# Clock_rev1.net
KiCad netlist of a schematic drawn in EAGLE
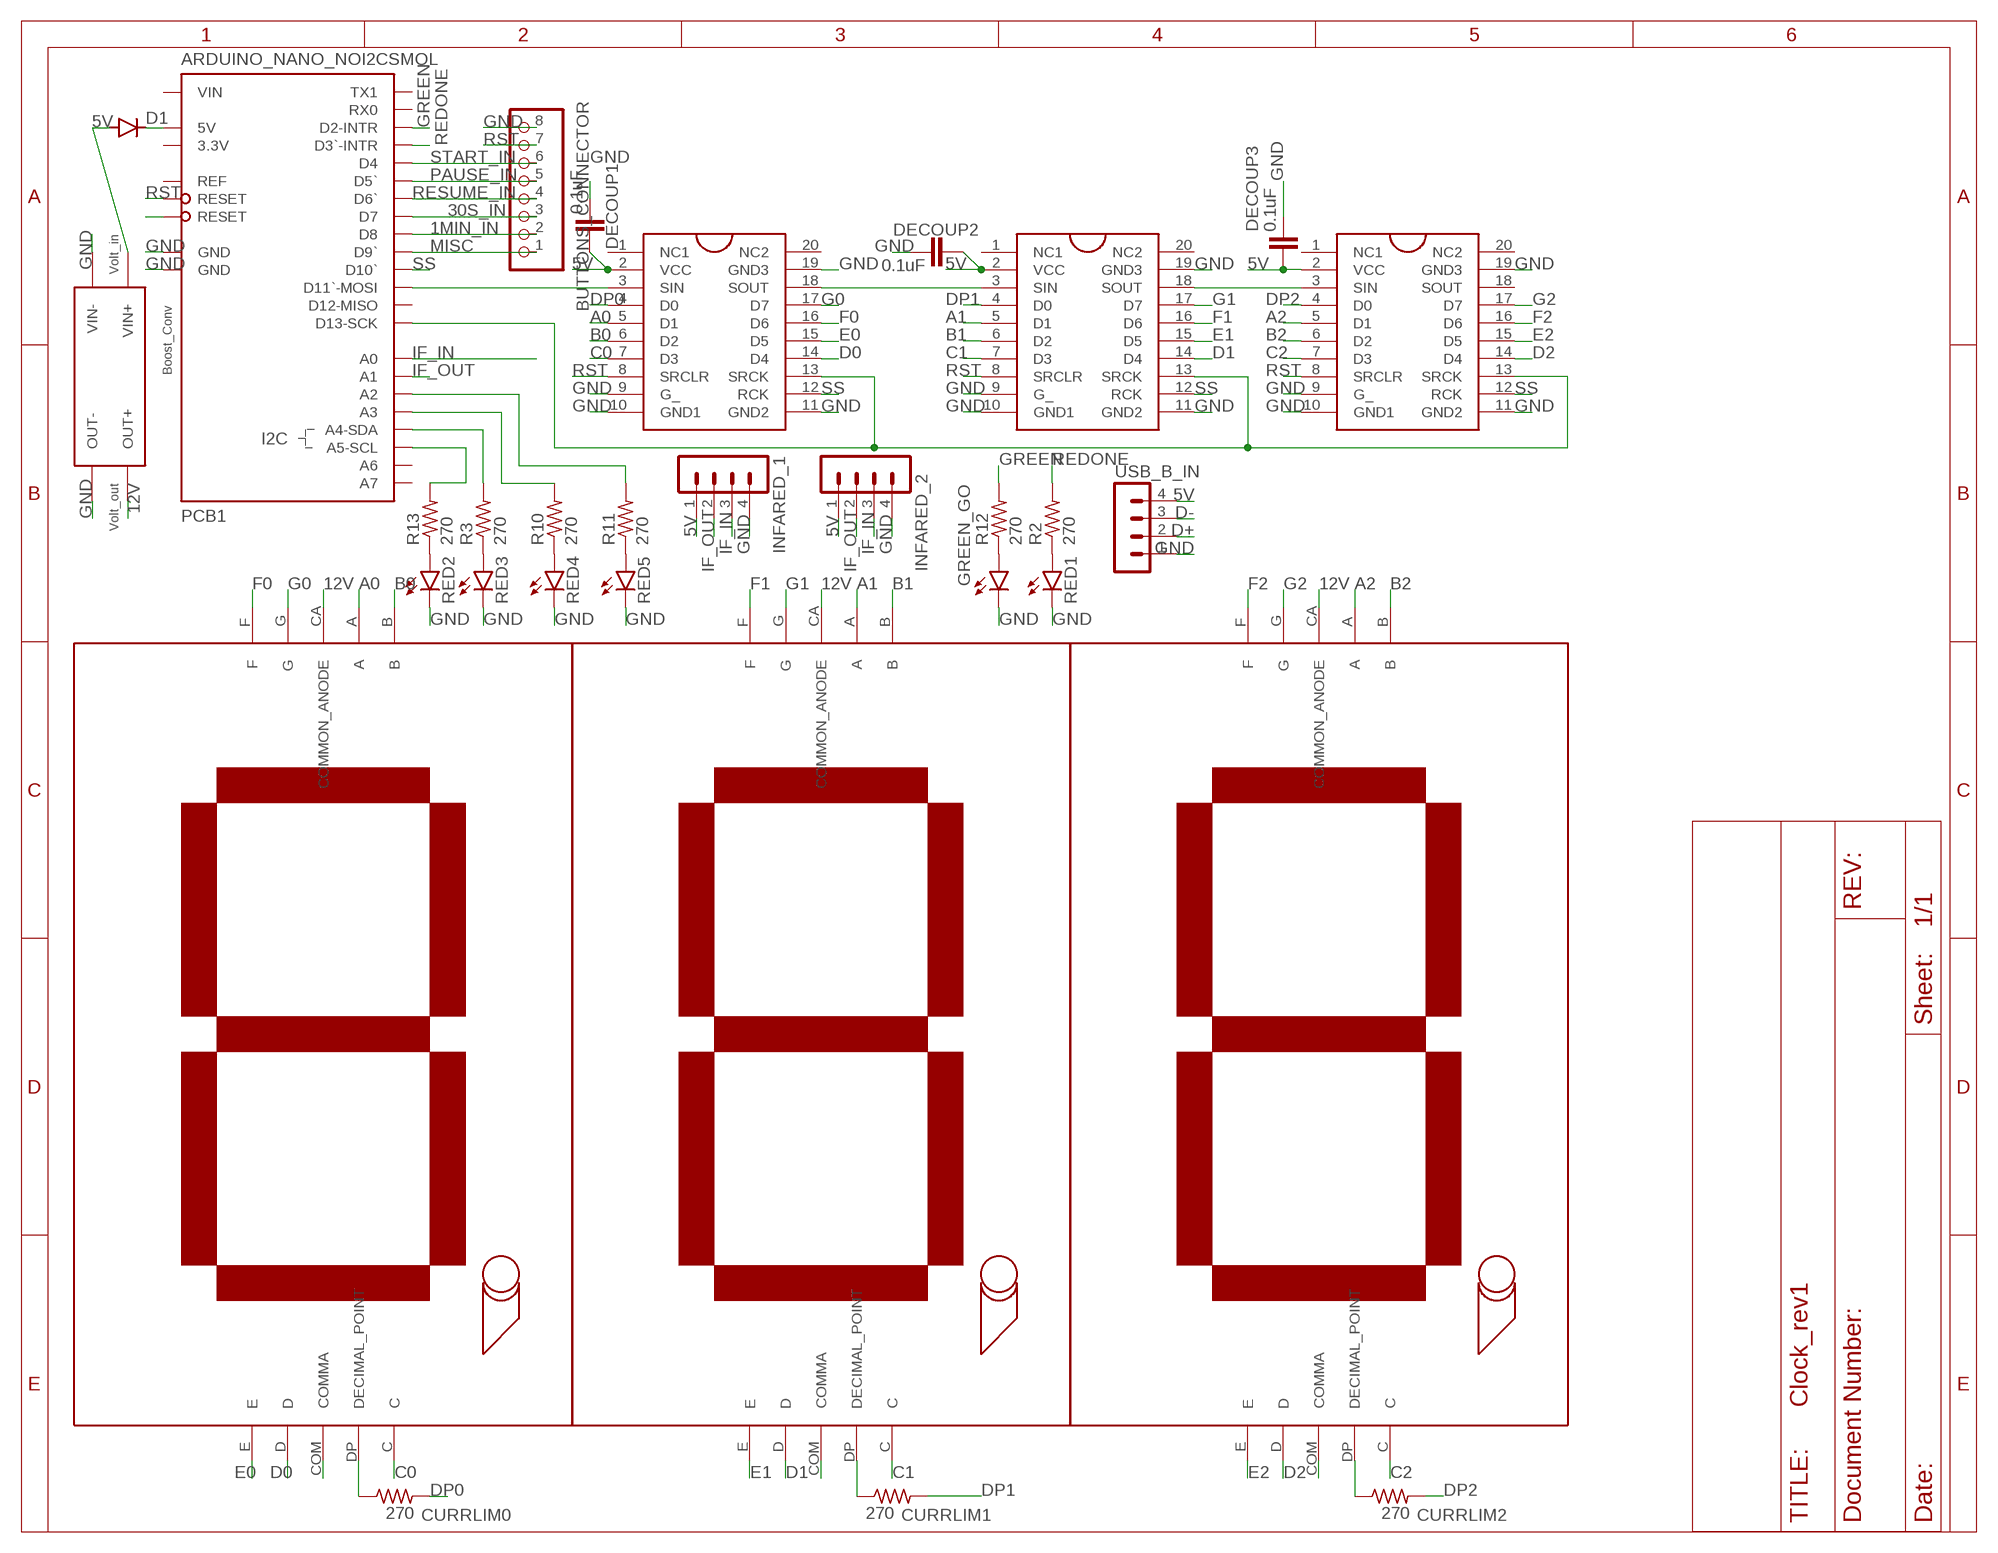
[diagram p0: schematic, sheet 1]

(export (version "E")
  (design (tool "Eeschema 10.0.6"))
  (components
    (comp (ref "BUTTONS_CONNECTOR")
      (value "PINHD-1X8/90")
      (footprint "eagle-import:1X08_90")
      (libsource (lib "eagle-import") (part "PINHD-1X8/90"))
    )
    (comp (ref "CURRLIM0")
      (value "270")
      (footprint "eagle-import:0207_10")
      (libsource (lib "eagle-import") (part "R-US_0207/10"))
    )
    (comp (ref "CURRLIM1")
      (value "270")
      (footprint "eagle-import:0207_10")
      (libsource (lib "eagle-import") (part "R-US_0207/10"))
    )
    (comp (ref "CURRLIM2")
      (value "270")
      (footprint "eagle-import:0207_10")
      (libsource (lib "eagle-import") (part "R-US_0207/10"))
    )
    (comp (ref "D1")
      (value "1N4148DO35-7")
      (footprint "eagle-import:DO35-7")
      (libsource (lib "eagle-import") (part "1N4148DO35-7"))
    )
    (comp (ref "DECOUP1")
      (value "0.1uF")
      (footprint "eagle-import:C2.5-2")
      (libsource (lib "eagle-import") (part "C2.5/2"))
    )
    (comp (ref "DECOUP2")
      (value "0.1uF")
      (footprint "eagle-import:C2.5-2")
      (libsource (lib "eagle-import") (part "C2.5/2"))
    )
    (comp (ref "DECOUP3")
      (value "0.1uF")
      (footprint "eagle-import:C2.5-2")
      (libsource (lib "eagle-import") (part "C2.5/2"))
    )
    (comp (ref "GREEN_GO")
      (value "LED5MM")
      (footprint "eagle-import:LED5MM")
      (libsource (lib "eagle-import") (part "LED5MM"))
    )
    (comp (ref "INFARED_1")
      (value "MA04-1")
      (footprint "eagle-import:MA04-1")
      (libsource (lib "eagle-import") (part "MA04-1"))
    )
    (comp (ref "INFARED_2")
      (value "MA04-1")
      (footprint "eagle-import:MA04-1")
      (libsource (lib "eagle-import") (part "MA04-1"))
    )
    (comp (ref "MINUTES")
      (value "7SEG_LED_A-3001SR")
      (footprint "eagle-import:7SEG_LED")
      (libsource (lib "eagle-import") (part "7SEG_LED_A-3001SR"))
    )
    (comp (ref "PCB1")
      (value "ARDUINO_NANO_NOI2CSMOL")
      (footprint "eagle-import:ARDUINO_NANO_SMOL")
      (libsource (lib "eagle-import") (part "ARDUINO_NANO_NOI2CSMOL"))
    )
    (comp (ref "R2")
      (value "270")
      (footprint "eagle-import:0207_10")
      (libsource (lib "eagle-import") (part "R-US_0207/10"))
    )
    (comp (ref "R3")
      (value "270")
      (footprint "eagle-import:0207_10")
      (libsource (lib "eagle-import") (part "R-US_0207/10"))
    )
    (comp (ref "R10")
      (value "270")
      (footprint "eagle-import:0207_10")
      (libsource (lib "eagle-import") (part "R-US_0207/10"))
    )
    (comp (ref "R11")
      (value "270")
      (footprint "eagle-import:0207_10")
      (libsource (lib "eagle-import") (part "R-US_0207/10"))
    )
    (comp (ref "R12")
      (value "270")
      (footprint "eagle-import:0207_10")
      (libsource (lib "eagle-import") (part "R-US_0207/10"))
    )
    (comp (ref "R13")
      (value "270")
      (footprint "eagle-import:0207_10")
      (libsource (lib "eagle-import") (part "R-US_0207/10"))
    )
    (comp (ref "RED1")
      (value "LED5MM")
      (footprint "eagle-import:LED5MM")
      (libsource (lib "eagle-import") (part "LED5MM"))
    )
    (comp (ref "RED2")
      (value "LED5MM")
      (footprint "eagle-import:LED5MM")
      (libsource (lib "eagle-import") (part "LED5MM"))
    )
    (comp (ref "RED3")
      (value "LED5MM")
      (footprint "eagle-import:LED5MM")
      (libsource (lib "eagle-import") (part "LED5MM"))
    )
    (comp (ref "RED4")
      (value "LED5MM")
      (footprint "eagle-import:LED5MM")
      (libsource (lib "eagle-import") (part "LED5MM"))
    )
    (comp (ref "RED5")
      (value "LED5MM")
      (footprint "eagle-import:LED5MM")
      (libsource (lib "eagle-import") (part "LED5MM"))
    )
    (comp (ref "SECONDS_ONES")
      (value "7SEG_LED_A-3001SR")
      (footprint "eagle-import:7SEG_LED")
      (libsource (lib "eagle-import") (part "7SEG_LED_A-3001SR"))
    )
    (comp (ref "SECONDS_TENS")
      (value "7SEG_LED_A-3001SR")
      (footprint "eagle-import:7SEG_LED")
      (libsource (lib "eagle-import") (part "7SEG_LED_A-3001SR"))
    )
    (comp (ref "SP0")
      (value "SHIFT_REGISTER_TPIC6C595")
      (footprint "eagle-import:SHIFT_REGISTER")
      (libsource (lib "eagle-import") (part "SHIFT_REGISTER_TPIC6C595"))
    )
    (comp (ref "SP1")
      (value "SHIFT_REGISTER_TPIC6C595")
      (footprint "eagle-import:SHIFT_REGISTER")
      (libsource (lib "eagle-import") (part "SHIFT_REGISTER_TPIC6C595"))
    )
    (comp (ref "SP2")
      (value "SHIFT_REGISTER_TPIC6C595")
      (footprint "eagle-import:SHIFT_REGISTER")
      (libsource (lib "eagle-import") (part "SHIFT_REGISTER_TPIC6C595"))
    )
    (comp (ref "U$4")
      (value "BOOST_CONV")
      (footprint "eagle-import:BOOST_CONV")
      (libsource (lib "eagle-import") (part "BOOST_CONV"))
    )
    (comp (ref "USB_B_IN")
      (value "MA04-1")
      (footprint "eagle-import:MA04-1")
      (libsource (lib "eagle-import") (part "MA04-1"))
    )
  )
  (nets
    (net (code "1") (name "/1MIN_IN") (class "Default")
      (node (ref "BUTTONS_CONNECTOR") (pin "2") (pinfunction "2_2") (pintype "passive"))
      (node (ref "PCB1") (pin "D8") (pinfunction "D8_D8") (pintype "bidirectional"))
    )
    (net (code "2") (name "/5V") (class "Default")
      (node (ref "D1") (pin "A") (pinfunction "A_A") (pintype "passive"))
      (node (ref "DECOUP1") (pin "2") (pinfunction "2_2") (pintype "passive"))
      (node (ref "DECOUP2") (pin "2") (pinfunction "2_2") (pintype "passive"))
      (node (ref "DECOUP3") (pin "2") (pinfunction "2_2") (pintype "passive"))
      (node (ref "INFARED_1") (pin "1") (pinfunction "1_1") (pintype "passive"))
      (node (ref "INFARED_2") (pin "1") (pinfunction "1_1") (pintype "passive"))
      (node (ref "SP0") (pin "2") (pinfunction "VCC_2") (pintype "bidirectional"))
      (node (ref "SP1") (pin "2") (pinfunction "VCC_2") (pintype "bidirectional"))
      (node (ref "SP2") (pin "2") (pinfunction "VCC_2") (pintype "bidirectional"))
      (node (ref "U$4") (pin "P$2") (pinfunction "VIN+_P$2") (pintype "bidirectional"))
      (node (ref "USB_B_IN") (pin "4") (pinfunction "4_4") (pintype "passive"))
    )
    (net (code "3") (name "/12V") (class "Default")
      (node (ref "MINUTES") (pin "CA") (pinfunction "COMMON_ANODE_CA") (pintype "bidirectional"))
      (node (ref "SECONDS_ONES") (pin "CA") (pinfunction "COMMON_ANODE_CA") (pintype "bidirectional"))
      (node (ref "SECONDS_TENS") (pin "CA") (pinfunction "COMMON_ANODE_CA") (pintype "bidirectional"))
      (node (ref "U$4") (pin "P$3") (pinfunction "OUT+_P$3") (pintype "bidirectional"))
    )
    (net (code "4") (name "/30S_IN") (class "Default")
      (node (ref "BUTTONS_CONNECTOR") (pin "3") (pinfunction "3_3") (pintype "passive"))
      (node (ref "PCB1") (pin "D7") (pinfunction "D7_D7") (pintype "bidirectional"))
    )
    (net (code "5") (name "/A0") (class "Default")
      (node (ref "MINUTES") (pin "A") (pinfunction "A_A") (pintype "bidirectional"))
      (node (ref "SP0") (pin "5") (pinfunction "D1_5") (pintype "bidirectional"))
    )
    (net (code "6") (name "/A1") (class "Default")
      (node (ref "SECONDS_TENS") (pin "A") (pinfunction "A_A") (pintype "bidirectional"))
      (node (ref "SP1") (pin "5") (pinfunction "D1_5") (pintype "bidirectional"))
    )
    (net (code "7") (name "/A2") (class "Default")
      (node (ref "SECONDS_ONES") (pin "A") (pinfunction "A_A") (pintype "bidirectional"))
      (node (ref "SP2") (pin "5") (pinfunction "D1_5") (pintype "bidirectional"))
    )
    (net (code "8") (name "/B0") (class "Default")
      (node (ref "MINUTES") (pin "B") (pinfunction "B_B") (pintype "bidirectional"))
      (node (ref "SP0") (pin "6") (pinfunction "D2_6") (pintype "bidirectional"))
    )
    (net (code "9") (name "/B1") (class "Default")
      (node (ref "SECONDS_TENS") (pin "B") (pinfunction "B_B") (pintype "bidirectional"))
      (node (ref "SP1") (pin "6") (pinfunction "D2_6") (pintype "bidirectional"))
    )
    (net (code "10") (name "/B2") (class "Default")
      (node (ref "SECONDS_ONES") (pin "B") (pinfunction "B_B") (pintype "bidirectional"))
      (node (ref "SP2") (pin "6") (pinfunction "D2_6") (pintype "bidirectional"))
    )
    (net (code "11") (name "/C0") (class "Default")
      (node (ref "MINUTES") (pin "C") (pinfunction "C_C") (pintype "bidirectional"))
      (node (ref "SP0") (pin "7") (pinfunction "D3_7") (pintype "bidirectional"))
    )
    (net (code "12") (name "/C1") (class "Default")
      (node (ref "SECONDS_TENS") (pin "C") (pinfunction "C_C") (pintype "bidirectional"))
      (node (ref "SP1") (pin "7") (pinfunction "D3_7") (pintype "bidirectional"))
    )
    (net (code "13") (name "/C2") (class "Default")
      (node (ref "SECONDS_ONES") (pin "C") (pinfunction "C_C") (pintype "bidirectional"))
      (node (ref "SP2") (pin "7") (pinfunction "D3_7") (pintype "bidirectional"))
    )
    (net (code "14") (name "/D+") (class "Default")
      (node (ref "USB_B_IN") (pin "2") (pinfunction "2_2") (pintype "passive"))
    )
    (net (code "15") (name "/D-") (class "Default")
      (node (ref "USB_B_IN") (pin "3") (pinfunction "3_3") (pintype "passive"))
    )
    (net (code "16") (name "/D0") (class "Default")
      (node (ref "MINUTES") (pin "D") (pinfunction "D_D") (pintype "bidirectional"))
      (node (ref "SP0") (pin "14") (pinfunction "D4_14") (pintype "bidirectional"))
    )
    (net (code "17") (name "/D1") (class "Default")
      (node (ref "SECONDS_TENS") (pin "D") (pinfunction "D_D") (pintype "bidirectional"))
      (node (ref "SP1") (pin "14") (pinfunction "D4_14") (pintype "bidirectional"))
    )
    (net (code "18") (name "/D2") (class "Default")
      (node (ref "SECONDS_ONES") (pin "D") (pinfunction "D_D") (pintype "bidirectional"))
      (node (ref "SP2") (pin "14") (pinfunction "D4_14") (pintype "bidirectional"))
    )
    (net (code "19") (name "/DP0") (class "Default")
      (node (ref "CURRLIM0") (pin "2") (pinfunction "2_2") (pintype "passive"))
      (node (ref "SP0") (pin "4") (pinfunction "D0_4") (pintype "bidirectional"))
    )
    (net (code "20") (name "/DP1") (class "Default")
      (node (ref "CURRLIM1") (pin "2") (pinfunction "2_2") (pintype "passive"))
      (node (ref "SP1") (pin "4") (pinfunction "D0_4") (pintype "bidirectional"))
    )
    (net (code "21") (name "/DP2") (class "Default")
      (node (ref "CURRLIM2") (pin "2") (pinfunction "2_2") (pintype "passive"))
      (node (ref "SP2") (pin "4") (pinfunction "D0_4") (pintype "bidirectional"))
    )
    (net (code "22") (name "/E0") (class "Default")
      (node (ref "MINUTES") (pin "E") (pinfunction "E_E") (pintype "bidirectional"))
      (node (ref "SP0") (pin "15") (pinfunction "D5_15") (pintype "bidirectional"))
    )
    (net (code "23") (name "/E1") (class "Default")
      (node (ref "SECONDS_TENS") (pin "E") (pinfunction "E_E") (pintype "bidirectional"))
      (node (ref "SP1") (pin "15") (pinfunction "D5_15") (pintype "bidirectional"))
    )
    (net (code "24") (name "/E2") (class "Default")
      (node (ref "SECONDS_ONES") (pin "E") (pinfunction "E_E") (pintype "bidirectional"))
      (node (ref "SP2") (pin "15") (pinfunction "D5_15") (pintype "bidirectional"))
    )
    (net (code "25") (name "/F0") (class "Default")
      (node (ref "MINUTES") (pin "F") (pinfunction "F_F") (pintype "bidirectional"))
      (node (ref "SP0") (pin "16") (pinfunction "D6_16") (pintype "bidirectional"))
    )
    (net (code "26") (name "/F1") (class "Default")
      (node (ref "SECONDS_TENS") (pin "F") (pinfunction "F_F") (pintype "bidirectional"))
      (node (ref "SP1") (pin "16") (pinfunction "D6_16") (pintype "bidirectional"))
    )
    (net (code "27") (name "/F2") (class "Default")
      (node (ref "SECONDS_ONES") (pin "F") (pinfunction "F_F") (pintype "bidirectional"))
      (node (ref "SP2") (pin "16") (pinfunction "D6_16") (pintype "bidirectional"))
    )
    (net (code "28") (name "/G0") (class "Default")
      (node (ref "MINUTES") (pin "G") (pinfunction "G_G") (pintype "bidirectional"))
      (node (ref "SP0") (pin "17") (pinfunction "D7_17") (pintype "bidirectional"))
    )
    (net (code "29") (name "/G1") (class "Default")
      (node (ref "SECONDS_TENS") (pin "G") (pinfunction "G_G") (pintype "bidirectional"))
      (node (ref "SP1") (pin "17") (pinfunction "D7_17") (pintype "bidirectional"))
    )
    (net (code "30") (name "/G2") (class "Default")
      (node (ref "SECONDS_ONES") (pin "G") (pinfunction "G_G") (pintype "bidirectional"))
      (node (ref "SP2") (pin "17") (pinfunction "D7_17") (pintype "bidirectional"))
    )
    (net (code "31") (name "/GND") (class "Default")
      (node (ref "BUTTONS_CONNECTOR") (pin "8") (pinfunction "8_8") (pintype "passive"))
      (node (ref "DECOUP1") (pin "1") (pinfunction "1_1") (pintype "passive"))
      (node (ref "DECOUP2") (pin "1") (pinfunction "1_1") (pintype "passive"))
      (node (ref "DECOUP3") (pin "1") (pinfunction "1_1") (pintype "passive"))
      (node (ref "GREEN_GO") (pin "K") (pinfunction "C_K") (pintype "passive"))
      (node (ref "INFARED_1") (pin "4") (pinfunction "4_4") (pintype "passive"))
      (node (ref "INFARED_2") (pin "4") (pinfunction "4_4") (pintype "passive"))
      (node (ref "PCB1") (pin "GND") (pinfunction "GND_GND") (pintype "bidirectional"))
      (node (ref "PCB1") (pin "GND@2") (pinfunction "GND_GND@2") (pintype "bidirectional"))
      (node (ref "RED1") (pin "K") (pinfunction "C_K") (pintype "passive"))
      (node (ref "RED2") (pin "K") (pinfunction "C_K") (pintype "passive"))
      (node (ref "RED3") (pin "K") (pinfunction "C_K") (pintype "passive"))
      (node (ref "RED4") (pin "K") (pinfunction "C_K") (pintype "passive"))
      (node (ref "RED5") (pin "K") (pinfunction "C_K") (pintype "passive"))
      (node (ref "SP0") (pin "10") (pinfunction "GND1_10") (pintype "bidirectional"))
      (node (ref "SP0") (pin "11") (pinfunction "GND2_11") (pintype "bidirectional"))
      (node (ref "SP0") (pin "19") (pinfunction "GND3_19") (pintype "bidirectional"))
      (node (ref "SP0") (pin "9") (pinfunction "G__9") (pintype "bidirectional"))
      (node (ref "SP1") (pin "10") (pinfunction "GND1_10") (pintype "bidirectional"))
      (node (ref "SP1") (pin "11") (pinfunction "GND2_11") (pintype "bidirectional"))
      (node (ref "SP1") (pin "19") (pinfunction "GND3_19") (pintype "bidirectional"))
      (node (ref "SP1") (pin "9") (pinfunction "G__9") (pintype "bidirectional"))
      (node (ref "SP2") (pin "10") (pinfunction "GND1_10") (pintype "bidirectional"))
      (node (ref "SP2") (pin "11") (pinfunction "GND2_11") (pintype "bidirectional"))
      (node (ref "SP2") (pin "19") (pinfunction "GND3_19") (pintype "bidirectional"))
      (node (ref "SP2") (pin "9") (pinfunction "G__9") (pintype "bidirectional"))
      (node (ref "U$4") (pin "P$1") (pinfunction "VIN-_P$1") (pintype "bidirectional"))
      (node (ref "U$4") (pin "P$4") (pinfunction "OUT-_P$4") (pintype "bidirectional"))
      (node (ref "USB_B_IN") (pin "1") (pinfunction "1_1") (pintype "passive"))
    )
    (net (code "32") (name "/GREEN") (class "Default")
      (node (ref "PCB1") (pin "D2") (pinfunction "D2-INTR_D2") (pintype "bidirectional"))
      (node (ref "R12") (pin "2") (pinfunction "2_2") (pintype "passive"))
    )
    (net (code "33") (name "/IF_IN") (class "Default")
      (node (ref "INFARED_1") (pin "3") (pinfunction "3_3") (pintype "passive"))
      (node (ref "INFARED_2") (pin "3") (pinfunction "3_3") (pintype "passive"))
      (node (ref "PCB1") (pin "A0") (pinfunction "A0_A0") (pintype "bidirectional"))
    )
    (net (code "34") (name "/IF_OUT") (class "Default")
      (node (ref "INFARED_1") (pin "2") (pinfunction "2_2") (pintype "passive"))
      (node (ref "INFARED_2") (pin "2") (pinfunction "2_2") (pintype "passive"))
      (node (ref "PCB1") (pin "A1") (pinfunction "A1_A1") (pintype "bidirectional"))
    )
    (net (code "35") (name "/MISC") (class "Default")
      (node (ref "BUTTONS_CONNECTOR") (pin "1") (pinfunction "1_1") (pintype "passive"))
      (node (ref "PCB1") (pin "D9") (pinfunction "D9`_D9") (pintype "bidirectional"))
    )
    (net (code "36") (name "/PAUSE_IN") (class "Default")
      (node (ref "BUTTONS_CONNECTOR") (pin "5") (pinfunction "5_5") (pintype "passive"))
      (node (ref "PCB1") (pin "D5") (pinfunction "D5`_D5") (pintype "bidirectional"))
    )
    (net (code "37") (name "/REDONE") (class "Default")
      (node (ref "PCB1") (pin "D3") (pinfunction "D3`-INTR_D3") (pintype "bidirectional"))
      (node (ref "R2") (pin "2") (pinfunction "2_2") (pintype "passive"))
    )
    (net (code "38") (name "/RESUME_IN") (class "Default")
      (node (ref "BUTTONS_CONNECTOR") (pin "4") (pinfunction "4_4") (pintype "passive"))
      (node (ref "PCB1") (pin "D6") (pinfunction "D6`_D6") (pintype "bidirectional"))
    )
    (net (code "39") (name "/RST") (class "Default")
      (node (ref "BUTTONS_CONNECTOR") (pin "7") (pinfunction "7_7") (pintype "passive"))
      (node (ref "PCB1") (pin "RESET") (pinfunction "RESET_RESET") (pintype "bidirectional"))
      (node (ref "SP0") (pin "8") (pinfunction "SRCLR_8") (pintype "bidirectional"))
      (node (ref "SP1") (pin "8") (pinfunction "SRCLR_8") (pintype "bidirectional"))
      (node (ref "SP2") (pin "8") (pinfunction "SRCLR_8") (pintype "bidirectional"))
    )
    (net (code "40") (name "/SS") (class "Default")
      (node (ref "PCB1") (pin "D10") (pinfunction "D10`_D10") (pintype "bidirectional"))
      (node (ref "SP0") (pin "12") (pinfunction "RCK_12") (pintype "bidirectional"))
      (node (ref "SP1") (pin "12") (pinfunction "RCK_12") (pintype "bidirectional"))
      (node (ref "SP2") (pin "12") (pinfunction "RCK_12") (pintype "bidirectional"))
    )
    (net (code "41") (name "/START_IN") (class "Default")
      (node (ref "BUTTONS_CONNECTOR") (pin "6") (pinfunction "6_6") (pintype "passive"))
      (node (ref "PCB1") (pin "D4") (pinfunction "D4_D4") (pintype "bidirectional"))
    )
    (net (code "42") (name "Net-(D1-PadC)") (class "Default")
      (node (ref "D1") (pin "C") (pinfunction "C_C") (pintype "passive"))
      (node (ref "PCB1") (pin "5V") (pinfunction "5V_5V") (pintype "bidirectional"))
    )
    (net (code "43") (name "Net-(GREEN_GO-PadA)") (class "Default")
      (node (ref "GREEN_GO") (pin "A") (pinfunction "A_A") (pintype "passive"))
      (node (ref "R12") (pin "1") (pinfunction "1_1") (pintype "passive"))
    )
    (net (code "44") (name "Net-(MINUTES-DECIMAL_POINT)") (class "Default")
      (node (ref "CURRLIM0") (pin "1") (pinfunction "1_1") (pintype "passive"))
      (node (ref "MINUTES") (pin "DP") (pinfunction "DECIMAL_POINT_DP") (pintype "bidirectional"))
    )
    (net (code "45") (name "Net-(PCB1-A4-SDA)") (class "Default")
      (node (ref "PCB1") (pin "A4") (pinfunction "A4-SDA_A4") (pintype "bidirectional"))
      (node (ref "R3") (pin "2") (pinfunction "2_2") (pintype "passive"))
    )
    (net (code "46") (name "Net-(PCB1-A5-SCL)") (class "Default")
      (node (ref "PCB1") (pin "A5") (pinfunction "A5-SCL_A5") (pintype "bidirectional"))
      (node (ref "R13") (pin "2") (pinfunction "2_2") (pintype "passive"))
    )
    (net (code "47") (name "Net-(PCB1-D11`-MOSI)") (class "Default")
      (node (ref "PCB1") (pin "D11") (pinfunction "D11`-MOSI_D11") (pintype "bidirectional"))
      (node (ref "SP0") (pin "3") (pinfunction "SIN_3") (pintype "bidirectional"))
    )
    (net (code "48") (name "Net-(PCB1-D13-SCK)") (class "Default")
      (node (ref "PCB1") (pin "D13") (pinfunction "D13-SCK_D13") (pintype "bidirectional"))
      (node (ref "SP0") (pin "13") (pinfunction "SRCK_13") (pintype "bidirectional"))
      (node (ref "SP1") (pin "13") (pinfunction "SRCK_13") (pintype "bidirectional"))
      (node (ref "SP2") (pin "13") (pinfunction "SRCK_13") (pintype "bidirectional"))
    )
    (net (code "49") (name "Net-(PCB1-PadA2)") (class "Default")
      (node (ref "PCB1") (pin "A2") (pinfunction "A2_A2") (pintype "bidirectional"))
      (node (ref "R11") (pin "2") (pinfunction "2_2") (pintype "passive"))
    )
    (net (code "50") (name "Net-(PCB1-PadA3)") (class "Default")
      (node (ref "PCB1") (pin "A3") (pinfunction "A3_A3") (pintype "bidirectional"))
      (node (ref "R10") (pin "2") (pinfunction "2_2") (pintype "passive"))
    )
    (net (code "51") (name "Net-(R2-Pad1)") (class "Default")
      (node (ref "R2") (pin "1") (pinfunction "1_1") (pintype "passive"))
      (node (ref "RED1") (pin "A") (pinfunction "A_A") (pintype "passive"))
    )
    (net (code "52") (name "Net-(R3-Pad1)") (class "Default")
      (node (ref "R3") (pin "1") (pinfunction "1_1") (pintype "passive"))
      (node (ref "RED3") (pin "A") (pinfunction "A_A") (pintype "passive"))
    )
    (net (code "53") (name "Net-(R10-Pad1)") (class "Default")
      (node (ref "R10") (pin "1") (pinfunction "1_1") (pintype "passive"))
      (node (ref "RED4") (pin "A") (pinfunction "A_A") (pintype "passive"))
    )
    (net (code "54") (name "Net-(R11-Pad1)") (class "Default")
      (node (ref "R11") (pin "1") (pinfunction "1_1") (pintype "passive"))
      (node (ref "RED5") (pin "A") (pinfunction "A_A") (pintype "passive"))
    )
    (net (code "55") (name "Net-(R13-Pad1)") (class "Default")
      (node (ref "R13") (pin "1") (pinfunction "1_1") (pintype "passive"))
      (node (ref "RED2") (pin "A") (pinfunction "A_A") (pintype "passive"))
    )
    (net (code "56") (name "Net-(SECONDS_ONES-DECIMAL_POINT)") (class "Default")
      (node (ref "CURRLIM2") (pin "1") (pinfunction "1_1") (pintype "passive"))
      (node (ref "SECONDS_ONES") (pin "DP") (pinfunction "DECIMAL_POINT_DP") (pintype "bidirectional"))
    )
    (net (code "57") (name "Net-(SECONDS_TENS-DECIMAL_POINT)") (class "Default")
      (node (ref "CURRLIM1") (pin "1") (pinfunction "1_1") (pintype "passive"))
      (node (ref "SECONDS_TENS") (pin "DP") (pinfunction "DECIMAL_POINT_DP") (pintype "bidirectional"))
    )
    (net (code "58") (name "Net-(SP0-SOUT)") (class "Default")
      (node (ref "SP0") (pin "18") (pinfunction "SOUT_18") (pintype "bidirectional"))
      (node (ref "SP1") (pin "3") (pinfunction "SIN_3") (pintype "bidirectional"))
    )
    (net (code "59") (name "Net-(SP1-SOUT)") (class "Default")
      (node (ref "SP1") (pin "18") (pinfunction "SOUT_18") (pintype "bidirectional"))
      (node (ref "SP2") (pin "3") (pinfunction "SIN_3") (pintype "bidirectional"))
    )
    (net (code "60") (name "unconnected-(MINUTES-COMMA-PadCOM)") (class "Default")
      (node (ref "MINUTES") (pin "COM") (pinfunction "COMMA_COM") (pintype "bidirectional"))
    )
    (net (code "61") (name "unconnected-(PCB1-3.3V-Pad3V3)") (class "Default")
      (node (ref "PCB1") (pin "3V3") (pinfunction "3.3V_3V3") (pintype "bidirectional"))
    )
    (net (code "62") (name "unconnected-(PCB1-D12-MISO-PadD12)") (class "Default")
      (node (ref "PCB1") (pin "D12") (pinfunction "D12-MISO_D12") (pintype "bidirectional"))
    )
    (net (code "63") (name "unconnected-(PCB1-PadA6)") (class "Default")
      (node (ref "PCB1") (pin "A6") (pinfunction "A6_A6") (pintype "bidirectional"))
    )
    (net (code "64") (name "unconnected-(PCB1-PadA7)") (class "Default")
      (node (ref "PCB1") (pin "A7") (pinfunction "A7_A7") (pintype "bidirectional"))
    )
    (net (code "65") (name "unconnected-(PCB1-PadREF)") (class "Default")
      (node (ref "PCB1") (pin "REF") (pinfunction "REF_REF") (pintype "bidirectional"))
    )
    (net (code "66") (name "unconnected-(PCB1-PadRX0)") (class "Default")
      (node (ref "PCB1") (pin "RX0") (pinfunction "RX0_RX0") (pintype "bidirectional"))
    )
    (net (code "67") (name "unconnected-(PCB1-PadTX1)") (class "Default")
      (node (ref "PCB1") (pin "TX1") (pinfunction "TX1_TX1") (pintype "bidirectional"))
    )
    (net (code "68") (name "unconnected-(PCB1-PadVIN)") (class "Default")
      (node (ref "PCB1") (pin "VIN") (pinfunction "VIN_VIN") (pintype "bidirectional"))
    )
    (net (code "69") (name "unconnected-(PCB1-RESET-PadRESET@2)") (class "Default")
      (node (ref "PCB1") (pin "RESET@2") (pinfunction "RESET_RESET@2") (pintype "bidirectional"))
    )
    (net (code "70") (name "unconnected-(SECONDS_ONES-COMMA-PadCOM)") (class "Default")
      (node (ref "SECONDS_ONES") (pin "COM") (pinfunction "COMMA_COM") (pintype "bidirectional"))
    )
    (net (code "71") (name "unconnected-(SECONDS_TENS-COMMA-PadCOM)") (class "Default")
      (node (ref "SECONDS_TENS") (pin "COM") (pinfunction "COMMA_COM") (pintype "bidirectional"))
    )
    (net (code "72") (name "unconnected-(SP0-NC1-Pad1)") (class "Default")
      (node (ref "SP0") (pin "1") (pinfunction "NC1_1") (pintype "bidirectional"))
    )
    (net (code "73") (name "unconnected-(SP0-NC2-Pad20)") (class "Default")
      (node (ref "SP0") (pin "20") (pinfunction "NC2_20") (pintype "bidirectional"))
    )
    (net (code "74") (name "unconnected-(SP1-NC1-Pad1)") (class "Default")
      (node (ref "SP1") (pin "1") (pinfunction "NC1_1") (pintype "bidirectional"))
    )
    (net (code "75") (name "unconnected-(SP1-NC2-Pad20)") (class "Default")
      (node (ref "SP1") (pin "20") (pinfunction "NC2_20") (pintype "bidirectional"))
    )
    (net (code "76") (name "unconnected-(SP2-NC1-Pad1)") (class "Default")
      (node (ref "SP2") (pin "1") (pinfunction "NC1_1") (pintype "bidirectional"))
    )
    (net (code "77") (name "unconnected-(SP2-NC2-Pad20)") (class "Default")
      (node (ref "SP2") (pin "20") (pinfunction "NC2_20") (pintype "bidirectional"))
    )
    (net (code "78") (name "unconnected-(SP2-SOUT-Pad18)") (class "Default")
      (node (ref "SP2") (pin "18") (pinfunction "SOUT_18") (pintype "bidirectional"))
    )
  )
)
